# TempAndHumiditySensor.net
KiCad netlist of a schematic drawn in EAGLE
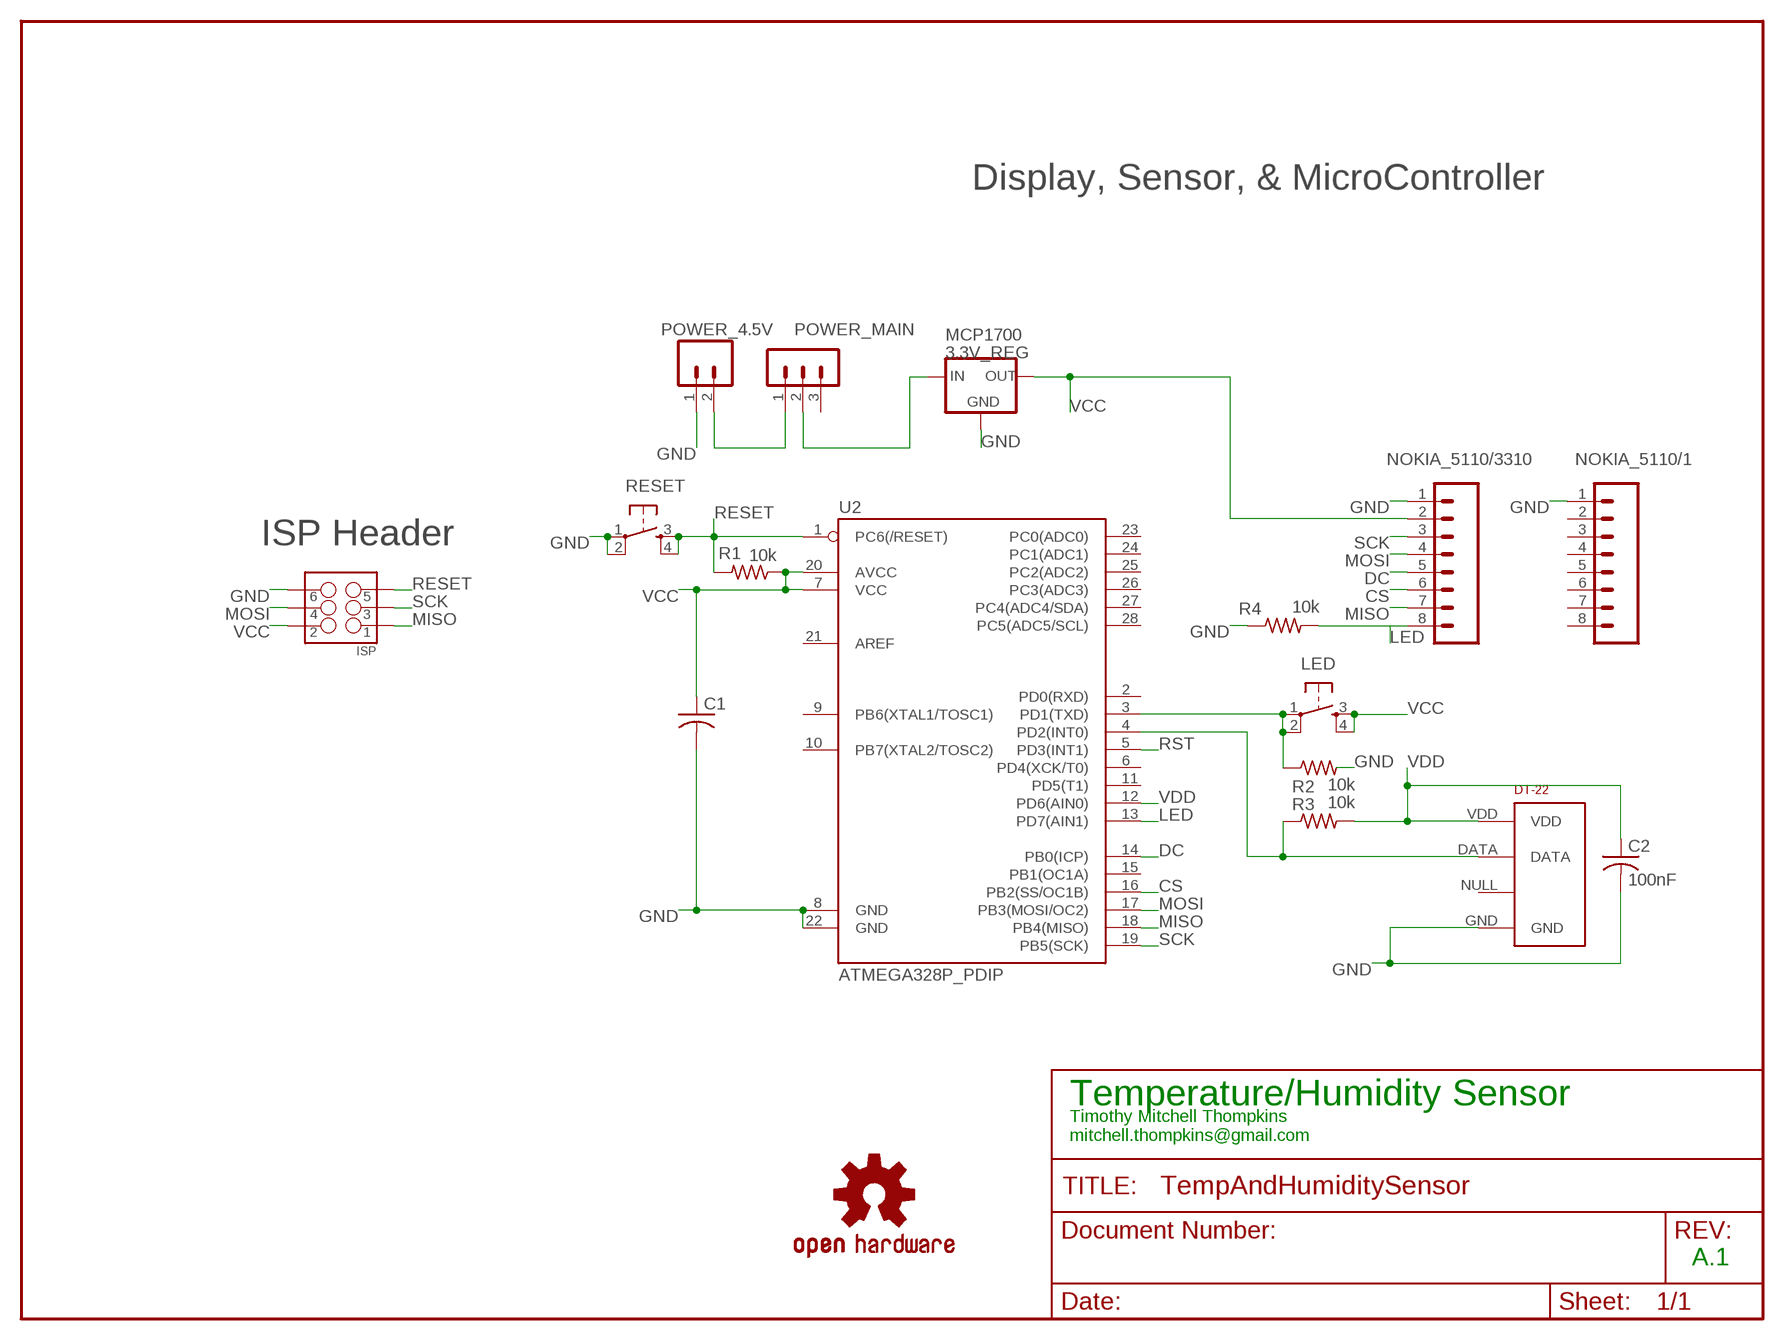
[diagram p0: schematic, sheet 1]

(export (version "E")
  (design (tool "Eeschema 10.0.6"))
  (components
    (comp (ref "C1")
      (value "C-US025-040X050")
      (footprint "eagle-import:C025-040X050")
      (libsource (lib "eagle-import") (part "C-US025-040X050"))
    )
    (comp (ref "C2")
      (value "100nF")
      (footprint "eagle-import:C025-040X050")
      (libsource (lib "eagle-import") (part "C-US025-040X050"))
    )
    (comp (ref "DT-22")
      (value "RHT03_DHT-22_AM2302RA")
      (footprint "eagle-import:RHT03_DHT-22_RA")
      (libsource (lib "eagle-import") (part "RHT03_DHT-22_AM2302RA"))
    )
    (comp (ref "ISP")
      (value "M03X2POGO_PINS")
      (footprint "eagle-import:2X3_POGO")
      (libsource (lib "eagle-import") (part "M03X2POGO_PINS"))
    )
    (comp (ref "LED")
      (value "RESET")
      (footprint "eagle-import:TACTILE-PTH")
      (libsource (lib "eagle-import") (part "TAC_SWITCHPTH"))
    )
    (comp (ref "LOGO2")
      (value "OSHW-LOGOS")
      (footprint "eagle-import:OSHW-LOGO-S")
      (libsource (lib "eagle-import") (part "OSHW-LOGOS"))
    )
    (comp (ref "MCP1700")
      (value "3.3V_REG")
      (footprint "eagle-import:TO92-INLINE")
      (libsource (lib "eagle-import") (part "MCP1700INLINE"))
    )
    (comp (ref "NOKIA_5110/1")
      (value "M08")
      (footprint "eagle-import:1X08_PIN1_NO_SILK")
      (libsource (lib "eagle-import") (part "M08"))
    )
    (comp (ref "NOKIA_5110/3310")
      (value "M08")
      (footprint "eagle-import:1X08_PIN1_NO_SILK")
      (libsource (lib "eagle-import") (part "M08"))
    )
    (comp (ref "POWER_4.5V")
      (value "M02LOCK_LONGPADS")
      (footprint "eagle-import:1X02_LOCK_LONGPADS")
      (libsource (lib "eagle-import") (part "M02LOCK_LONGPADS"))
    )
    (comp (ref "POWER_MAIN")
      (value "MA03-1")
      (footprint "eagle-import:MA03-1")
      (libsource (lib "eagle-import") (part "MA03-1"))
    )
    (comp (ref "R1")
      (value "10k")
      (footprint "eagle-import:0204_7")
      (libsource (lib "eagle-import") (part "R-US_0204/7"))
    )
    (comp (ref "R2")
      (value "10k")
      (footprint "eagle-import:0204_7")
      (libsource (lib "eagle-import") (part "R-US_0204/7"))
    )
    (comp (ref "R3")
      (value "10k")
      (footprint "eagle-import:0204_7")
      (libsource (lib "eagle-import") (part "R-US_0204/7"))
    )
    (comp (ref "R4")
      (value "10k")
      (footprint "eagle-import:0204_7")
      (libsource (lib "eagle-import") (part "R-US_0204/7"))
    )
    (comp (ref "RESET")
      (value "RESET")
      (footprint "eagle-import:TACTILE-PTH")
      (libsource (lib "eagle-import") (part "TAC_SWITCHPTH"))
    )
    (comp (ref "U2")
      (value "ATMEGA328P_PDIP")
      (footprint "eagle-import:DIL28-3")
      (libsource (lib "eagle-import") (part "ATMEGA328P_PDIP"))
    )
  )
  (nets
    (net (code "1") (name "/CS") (class "Default")
      (node (ref "NOKIA_5110/3310") (pin "6") (pinfunction "6_6") (pintype "passive"))
      (node (ref "U2") (pin "16") (pinfunction "PB2(SS/OC1B)_16") (pintype "bidirectional"))
    )
    (net (code "2") (name "/DC") (class "Default")
      (node (ref "NOKIA_5110/3310") (pin "5") (pinfunction "5_5") (pintype "passive"))
      (node (ref "U2") (pin "14") (pinfunction "PB0(ICP)_14") (pintype "bidirectional"))
    )
    (net (code "3") (name "/GND") (class "Default")
      (node (ref "C1") (pin "2") (pinfunction "2_2") (pintype "passive"))
      (node (ref "C2") (pin "2") (pinfunction "2_2") (pintype "passive"))
      (node (ref "DT-22") (pin "GND") (pinfunction "GND_GND") (pintype "power_in"))
      (node (ref "ISP") (pin "P$6") (pinfunction "6_P$6") (pintype "bidirectional"))
      (node (ref "MCP1700") (pin "1") (pinfunction "GND_1") (pintype "input"))
      (node (ref "NOKIA_5110/1") (pin "1") (pinfunction "1_1") (pintype "passive"))
      (node (ref "NOKIA_5110/3310") (pin "1") (pinfunction "1_1") (pintype "passive"))
      (node (ref "POWER_4.5V") (pin "1") (pinfunction "1_1") (pintype "passive"))
      (node (ref "R2") (pin "2") (pinfunction "2_2") (pintype "passive"))
      (node (ref "R4") (pin "1") (pinfunction "1_1") (pintype "passive"))
      (node (ref "RESET") (pin "1") (pinfunction "1_1") (pintype "passive"))
      (node (ref "RESET") (pin "2") (pinfunction "2_2") (pintype "passive"))
      (node (ref "U2") (pin "22") (pinfunction "GND_22") (pintype "bidirectional"))
      (node (ref "U2") (pin "8") (pinfunction "GND_8") (pintype "bidirectional"))
    )
    (net (code "4") (name "/LED") (class "Default")
      (node (ref "NOKIA_5110/3310") (pin "8") (pinfunction "8_8") (pintype "passive"))
      (node (ref "R4") (pin "2") (pinfunction "2_2") (pintype "passive"))
      (node (ref "U2") (pin "13") (pinfunction "PD7(AIN1)_13") (pintype "bidirectional"))
    )
    (net (code "5") (name "/MISO") (class "Default")
      (node (ref "ISP") (pin "P$1") (pinfunction "1_P$1") (pintype "bidirectional"))
      (node (ref "NOKIA_5110/3310") (pin "7") (pinfunction "7_7") (pintype "passive"))
      (node (ref "U2") (pin "18") (pinfunction "PB4(MISO)_18") (pintype "bidirectional"))
    )
    (net (code "6") (name "/MOSI") (class "Default")
      (node (ref "ISP") (pin "P$4") (pinfunction "4_P$4") (pintype "bidirectional"))
      (node (ref "NOKIA_5110/3310") (pin "4") (pinfunction "4_4") (pintype "passive"))
      (node (ref "U2") (pin "17") (pinfunction "PB3(MOSI/OC2)_17") (pintype "bidirectional"))
    )
    (net (code "7") (name "/RESET") (class "Default")
      (node (ref "ISP") (pin "P$5") (pinfunction "5_P$5") (pintype "bidirectional"))
      (node (ref "R1") (pin "2") (pinfunction "2_2") (pintype "passive"))
      (node (ref "RESET") (pin "3") (pinfunction "3_3") (pintype "passive"))
      (node (ref "RESET") (pin "4") (pinfunction "4_4") (pintype "passive"))
      (node (ref "U2") (pin "1") (pinfunction "PC6(/RESET)_1") (pintype "bidirectional"))
    )
    (net (code "8") (name "/RST") (class "Default")
      (node (ref "U2") (pin "5") (pinfunction "PD3(INT1)_5") (pintype "bidirectional"))
    )
    (net (code "9") (name "/SCK") (class "Default")
      (node (ref "ISP") (pin "P$3") (pinfunction "3_P$3") (pintype "bidirectional"))
      (node (ref "NOKIA_5110/3310") (pin "3") (pinfunction "3_3") (pintype "passive"))
      (node (ref "U2") (pin "19") (pinfunction "PB5(SCK)_19") (pintype "bidirectional"))
    )
    (net (code "10") (name "/VCC") (class "Default")
      (node (ref "C1") (pin "1") (pinfunction "1_1") (pintype "passive"))
      (node (ref "ISP") (pin "P$2") (pinfunction "2_P$2") (pintype "bidirectional"))
      (node (ref "LED") (pin "3") (pinfunction "3_3") (pintype "passive"))
      (node (ref "LED") (pin "4") (pinfunction "4_4") (pintype "passive"))
      (node (ref "MCP1700") (pin "3") (pinfunction "OUT_3") (pintype "passive"))
      (node (ref "NOKIA_5110/3310") (pin "2") (pinfunction "2_2") (pintype "passive"))
      (node (ref "R1") (pin "1") (pinfunction "1_1") (pintype "passive"))
      (node (ref "U2") (pin "20") (pinfunction "AVCC_20") (pintype "bidirectional"))
      (node (ref "U2") (pin "7") (pinfunction "VCC_7") (pintype "bidirectional"))
    )
    (net (code "11") (name "/VDD") (class "Default")
      (node (ref "C2") (pin "1") (pinfunction "1_1") (pintype "passive"))
      (node (ref "DT-22") (pin "VDD") (pinfunction "VDD_VDD") (pintype "power_in"))
      (node (ref "R3") (pin "2") (pinfunction "2_2") (pintype "passive"))
      (node (ref "U2") (pin "12") (pinfunction "PD6(AIN0)_12") (pintype "bidirectional"))
    )
    (net (code "12") (name "Net-(MCP1700-IN)") (class "Default")
      (node (ref "MCP1700") (pin "2") (pinfunction "IN_2") (pintype "input"))
      (node (ref "POWER_MAIN") (pin "2") (pinfunction "2_2") (pintype "passive"))
    )
    (net (code "13") (name "Net-(POWER_4.5V-Pad2)") (class "Default")
      (node (ref "POWER_4.5V") (pin "2") (pinfunction "2_2") (pintype "passive"))
      (node (ref "POWER_MAIN") (pin "1") (pinfunction "1_1") (pintype "passive"))
    )
    (net (code "14") (name "Net-(U2-PD1(TXD))") (class "Default")
      (node (ref "LED") (pin "1") (pinfunction "1_1") (pintype "passive"))
      (node (ref "LED") (pin "2") (pinfunction "2_2") (pintype "passive"))
      (node (ref "R2") (pin "1") (pinfunction "1_1") (pintype "passive"))
      (node (ref "U2") (pin "3") (pinfunction "PD1(TXD)_3") (pintype "bidirectional"))
    )
    (net (code "15") (name "Net-(U2-PD2(INT0))") (class "Default")
      (node (ref "DT-22") (pin "DATA") (pinfunction "DATA_DATA") (pintype "bidirectional"))
      (node (ref "R3") (pin "1") (pinfunction "1_1") (pintype "passive"))
      (node (ref "U2") (pin "4") (pinfunction "PD2(INT0)_4") (pintype "bidirectional"))
    )
    (net (code "16") (name "unconnected-(DT-22-PadNULL)") (class "Default")
      (node (ref "DT-22") (pin "NULL") (pinfunction "NULL_NULL") (pintype "no_connect"))
    )
    (net (code "17") (name "unconnected-(NOKIA_5110/1-Pad2)") (class "Default")
      (node (ref "NOKIA_5110/1") (pin "2") (pinfunction "2_2") (pintype "passive"))
    )
    (net (code "18") (name "unconnected-(NOKIA_5110/1-Pad3)") (class "Default")
      (node (ref "NOKIA_5110/1") (pin "3") (pinfunction "3_3") (pintype "passive"))
    )
    (net (code "19") (name "unconnected-(NOKIA_5110/1-Pad4)") (class "Default")
      (node (ref "NOKIA_5110/1") (pin "4") (pinfunction "4_4") (pintype "passive"))
    )
    (net (code "20") (name "unconnected-(NOKIA_5110/1-Pad5)") (class "Default")
      (node (ref "NOKIA_5110/1") (pin "5") (pinfunction "5_5") (pintype "passive"))
    )
    (net (code "21") (name "unconnected-(NOKIA_5110/1-Pad6)") (class "Default")
      (node (ref "NOKIA_5110/1") (pin "6") (pinfunction "6_6") (pintype "passive"))
    )
    (net (code "22") (name "unconnected-(NOKIA_5110/1-Pad7)") (class "Default")
      (node (ref "NOKIA_5110/1") (pin "7") (pinfunction "7_7") (pintype "passive"))
    )
    (net (code "23") (name "unconnected-(NOKIA_5110/1-Pad8)") (class "Default")
      (node (ref "NOKIA_5110/1") (pin "8") (pinfunction "8_8") (pintype "passive"))
    )
    (net (code "24") (name "unconnected-(POWER_MAIN-Pad3)") (class "Default")
      (node (ref "POWER_MAIN") (pin "3") (pinfunction "3_3") (pintype "passive"))
    )
    (net (code "25") (name "unconnected-(U2-AREF-Pad21)") (class "Default")
      (node (ref "U2") (pin "21") (pinfunction "AREF_21") (pintype "bidirectional"))
    )
    (net (code "26") (name "unconnected-(U2-PB1(OC1A)-Pad15)") (class "Default")
      (node (ref "U2") (pin "15") (pinfunction "PB1(OC1A)_15") (pintype "bidirectional"))
    )
    (net (code "27") (name "unconnected-(U2-PB6(XTAL1{slash}TOSC1)-Pad9)") (class "Default")
      (node (ref "U2") (pin "9") (pinfunction "PB6(XTAL1/TOSC1)_9") (pintype "bidirectional"))
    )
    (net (code "28") (name "unconnected-(U2-PB7(XTAL2{slash}TOSC2)-Pad10)") (class "Default")
      (node (ref "U2") (pin "10") (pinfunction "PB7(XTAL2/TOSC2)_10") (pintype "bidirectional"))
    )
    (net (code "29") (name "unconnected-(U2-PC0(ADC0)-Pad23)") (class "Default")
      (node (ref "U2") (pin "23") (pinfunction "PC0(ADC0)_23") (pintype "bidirectional"))
    )
    (net (code "30") (name "unconnected-(U2-PC1(ADC1)-Pad24)") (class "Default")
      (node (ref "U2") (pin "24") (pinfunction "PC1(ADC1)_24") (pintype "bidirectional"))
    )
    (net (code "31") (name "unconnected-(U2-PC2(ADC2)-Pad25)") (class "Default")
      (node (ref "U2") (pin "25") (pinfunction "PC2(ADC2)_25") (pintype "bidirectional"))
    )
    (net (code "32") (name "unconnected-(U2-PC3(ADC3)-Pad26)") (class "Default")
      (node (ref "U2") (pin "26") (pinfunction "PC3(ADC3)_26") (pintype "bidirectional"))
    )
    (net (code "33") (name "unconnected-(U2-PC4(ADC4{slash}SDA)-Pad27)") (class "Default")
      (node (ref "U2") (pin "27") (pinfunction "PC4(ADC4/SDA)_27") (pintype "bidirectional"))
    )
    (net (code "34") (name "unconnected-(U2-PC5(ADC5{slash}SCL)-Pad28)") (class "Default")
      (node (ref "U2") (pin "28") (pinfunction "PC5(ADC5/SCL)_28") (pintype "bidirectional"))
    )
    (net (code "35") (name "unconnected-(U2-PD0(RXD)-Pad2)") (class "Default")
      (node (ref "U2") (pin "2") (pinfunction "PD0(RXD)_2") (pintype "bidirectional"))
    )
    (net (code "36") (name "unconnected-(U2-PD4(XCK{slash}T0)-Pad6)") (class "Default")
      (node (ref "U2") (pin "6") (pinfunction "PD4(XCK/T0)_6") (pintype "bidirectional"))
    )
    (net (code "37") (name "unconnected-(U2-PD5(T1)-Pad11)") (class "Default")
      (node (ref "U2") (pin "11") (pinfunction "PD5(T1)_11") (pintype "bidirectional"))
    )
  )
)
